# Clock_Generator.net
KiCad netlist of a schematic drawn in Altium Designer
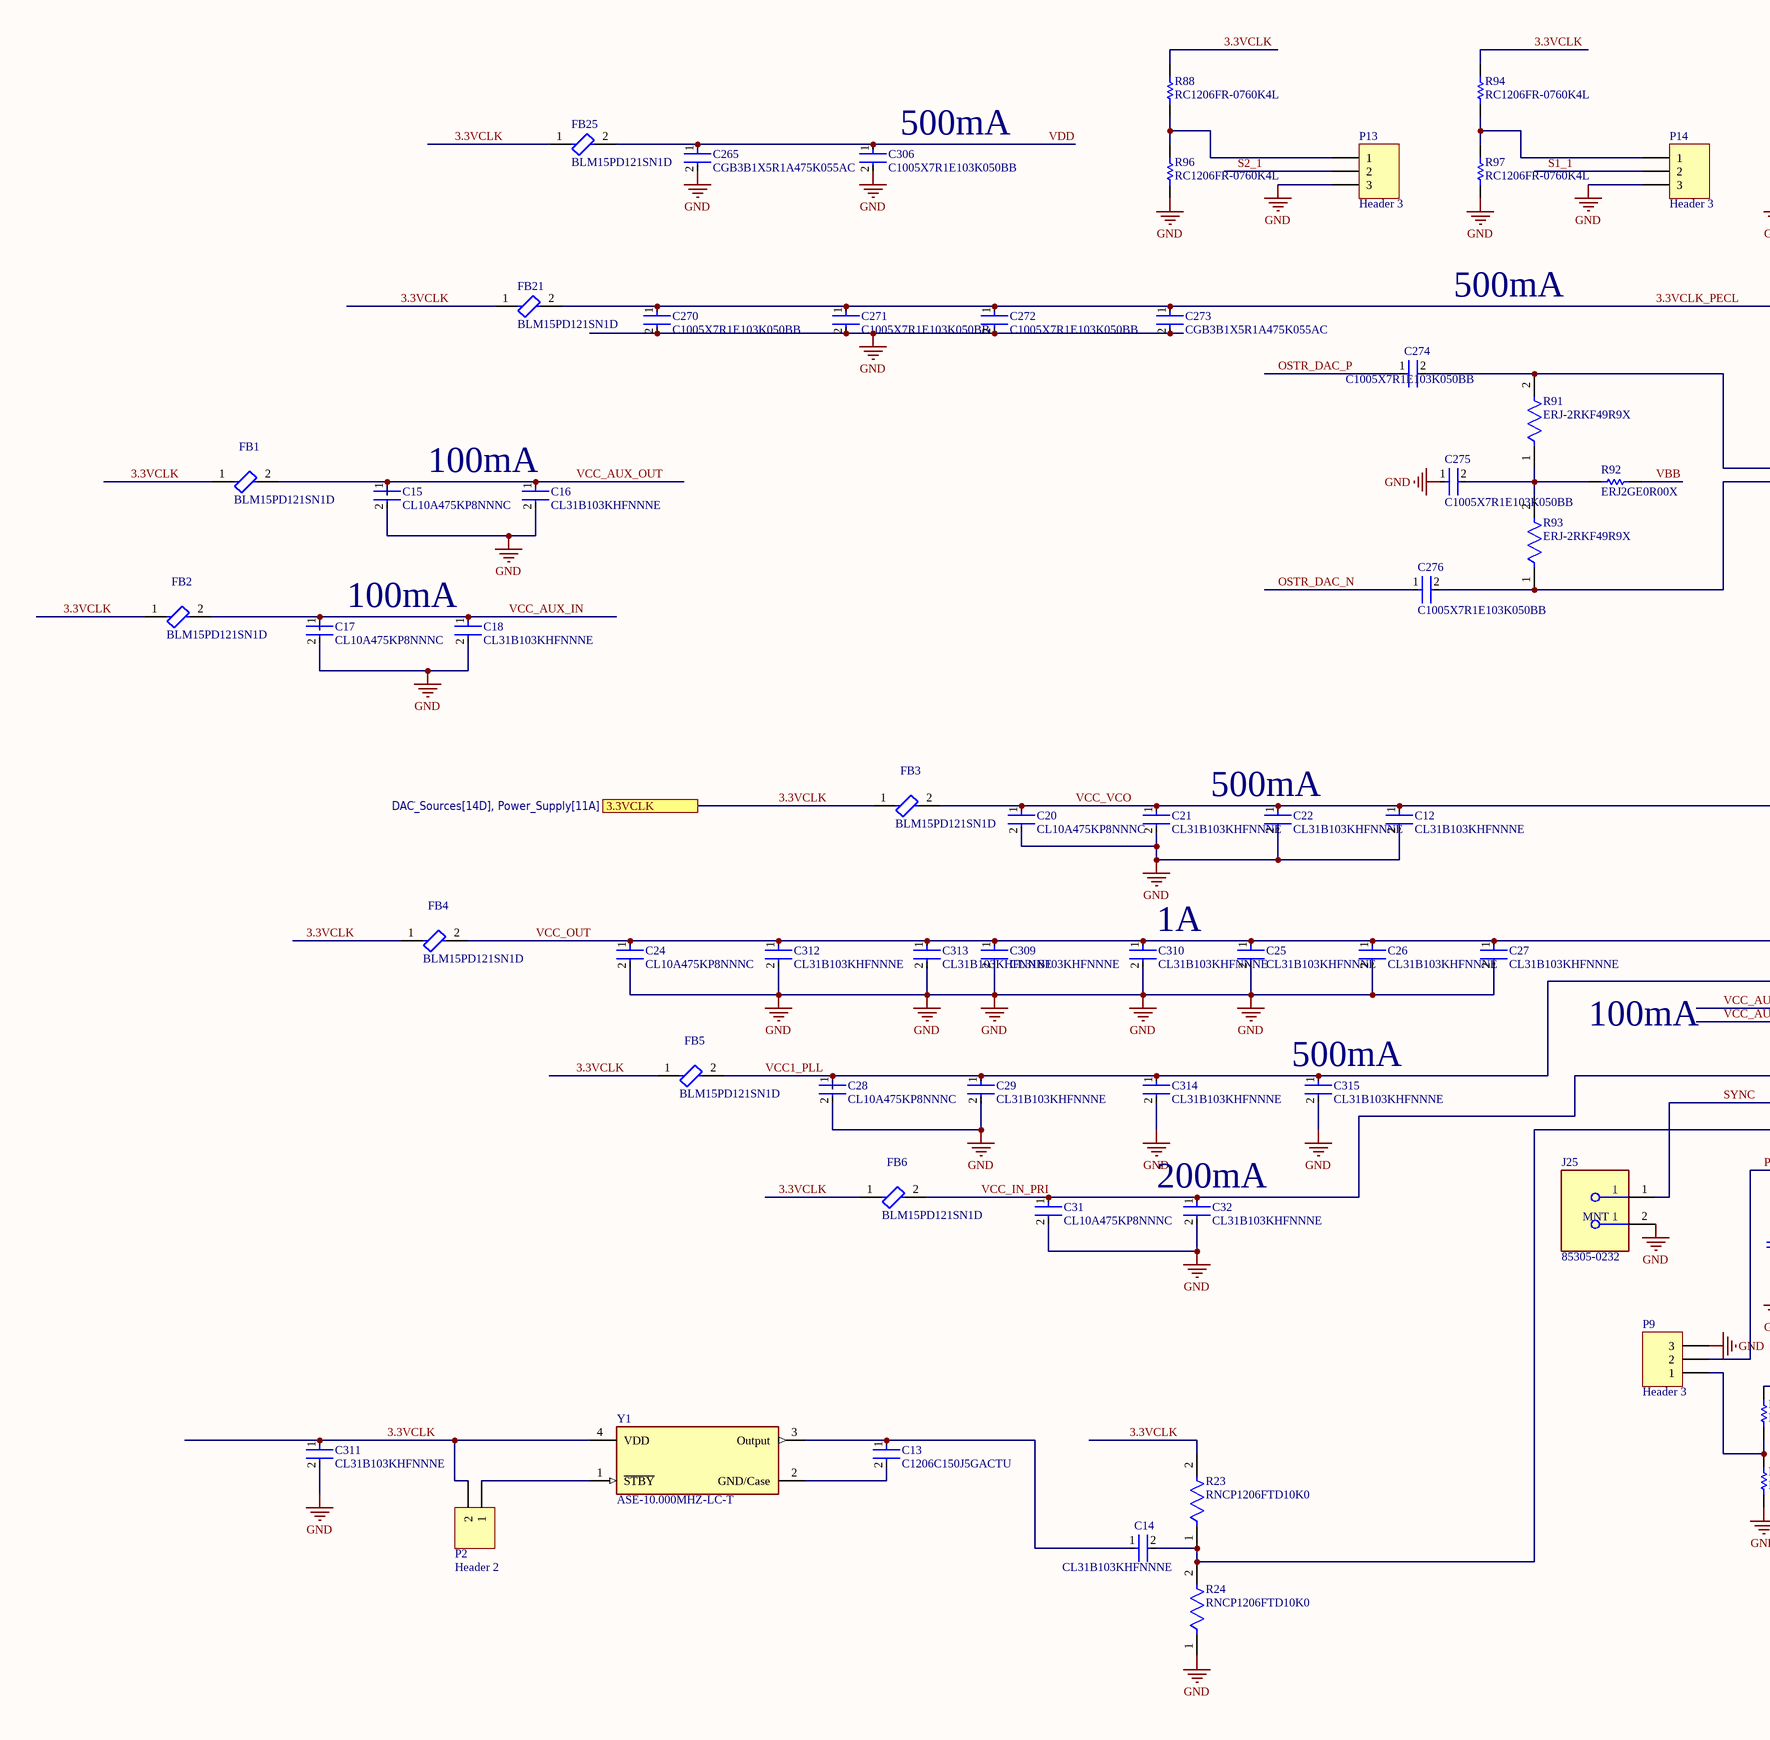
[diagram p0: Clock_Generator.SchDoc, left]
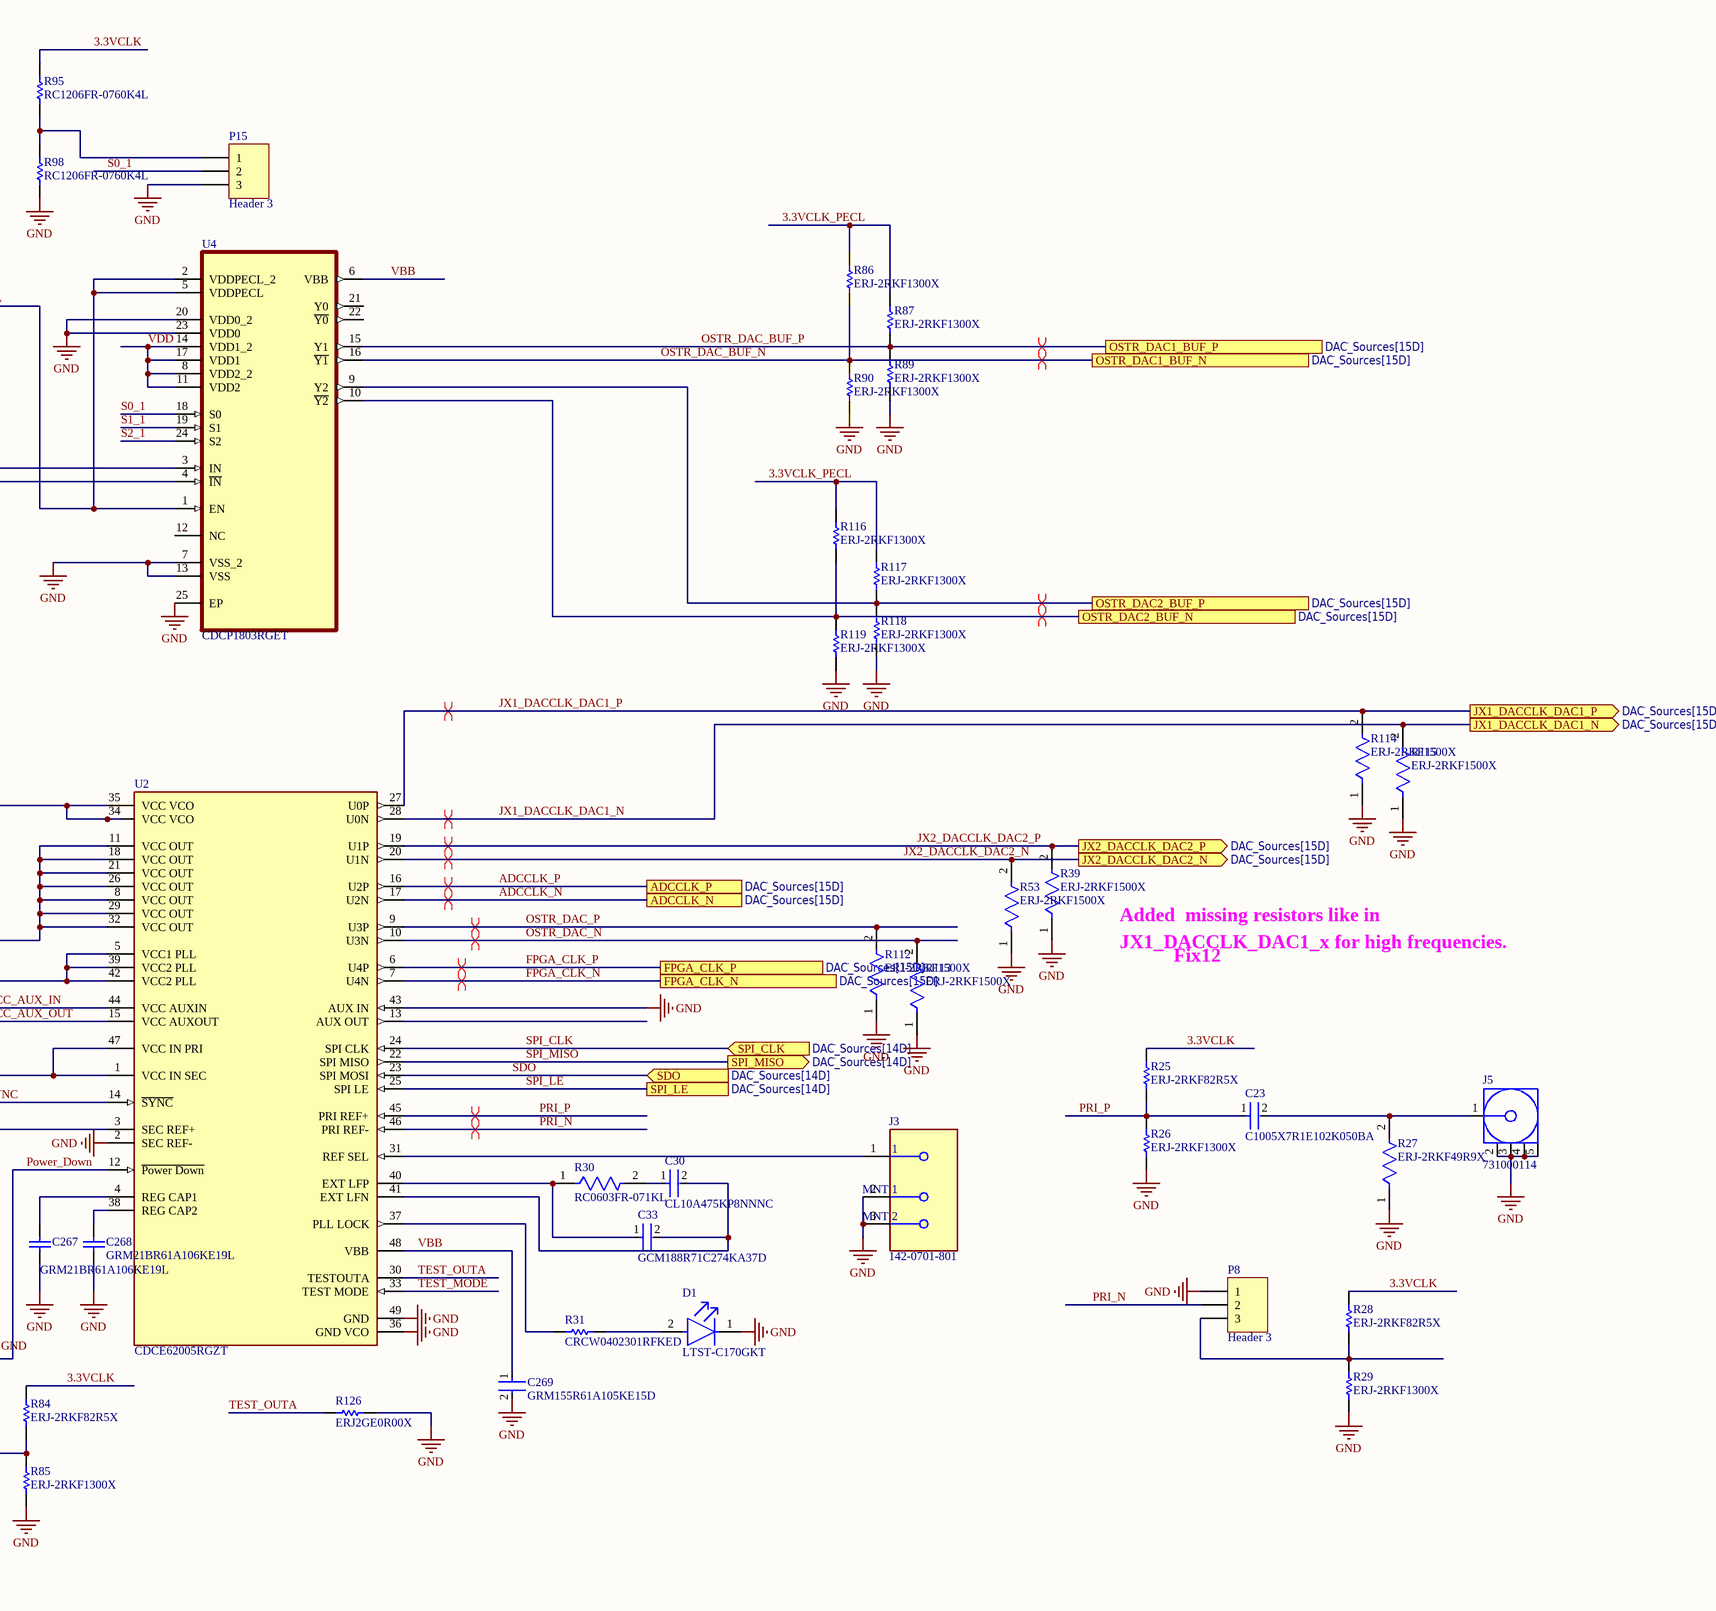
[diagram p1: Clock_Generator.SchDoc, right]

(export (version "E")
  (design (tool "Eeschema 10.0.6"))
  (components
    (comp (ref "C12")
      (value "CL31B103KHFNNNE")
      (footprint "C1206")
      (description "Cap Ceramic 10nF 630V X7R ±10% SMD 1206 +125°C Embossed T/R")
      (fields (field (name "TOLERANCE") "10%") (field (name "VOLTAGE") "630V"))
      (libsource (lib "DACֹֹ_Sources") (part "b4654b650e69147ec39a6b967a45e02"))
    )
    (comp (ref "C13")
      (value "C1206C150J5GACTU")
      (footprint "C1206")
      (description "1206 C 15pF Ceramic Multilayer Capacitor; 50 VDC; +125degC; C0G Dielec; +/-5%")
      (fields (field (name "TOLERANCE") "0.05") (field (name "MANUFACTURER") "KEMET"))
      (libsource (lib "DACֹֹ_Sources") (part "b4654b650e69147ec39a6b967a45e02"))
    )
    (comp (ref "C14")
      (value "CL31B103KHFNNNE")
      (footprint "C1206")
      (description "Cap Ceramic 10nF 630V X7R ±10% SMD 1206 +125°C Embossed T/R")
      (fields (field (name "TOLERANCE") "10%") (field (name "VOLTAGE") "630V"))
      (libsource (lib "DACֹֹ_Sources") (part "b4654b650e69147ec39a6b967a45e02"))
    )
    (comp (ref "C15")
      (value "CL10A475KP8NNNC")
      (footprint "C0603")
      (description "Cap Ceramic 4.7uF 10V X5R ±10% Pad SMD 0603 +85°C T/R")
      (fields (field (name "TOLERANCE") "10%"))
      (libsource (lib "DACֹֹ_Sources") (part "b4654b650e69147ec39a6b967a45e02"))
    )
    (comp (ref "C16")
      (value "CL31B103KHFNNNE")
      (footprint "C1206")
      (description "Cap Ceramic 10nF 630V X7R ±10% SMD 1206 +125°C Embossed T/R")
      (fields (field (name "TOLERANCE") "10%") (field (name "VOLTAGE") "630V"))
      (libsource (lib "DACֹֹ_Sources") (part "b4654b650e69147ec39a6b967a45e02"))
    )
    (comp (ref "C17")
      (value "CL10A475KP8NNNC")
      (footprint "C0603")
      (description "Cap Ceramic 4.7uF 10V X5R ±10% Pad SMD 0603 +85°C T/R")
      (fields (field (name "TOLERANCE") "10%"))
      (libsource (lib "DACֹֹ_Sources") (part "b4654b650e69147ec39a6b967a45e02"))
    )
    (comp (ref "C18")
      (value "CL31B103KHFNNNE")
      (footprint "C1206")
      (description "Cap Ceramic 10nF 630V X7R ±10% SMD 1206 +125°C Embossed T/R")
      (fields (field (name "TOLERANCE") "10%") (field (name "VOLTAGE") "630V"))
      (libsource (lib "DACֹֹ_Sources") (part "b4654b650e69147ec39a6b967a45e02"))
    )
    (comp (ref "C20")
      (value "CL10A475KP8NNNC")
      (footprint "C0603")
      (description "Cap Ceramic 4.7uF 10V X5R ±10% Pad SMD 0603 +85°C T/R")
      (fields (field (name "TOLERANCE") "10%"))
      (libsource (lib "DACֹֹ_Sources") (part "b4654b650e69147ec39a6b967a45e02"))
    )
    (comp (ref "C21")
      (value "CL31B103KHFNNNE")
      (footprint "C1206")
      (description "Cap Ceramic 10nF 630V X7R ±10% SMD 1206 +125°C Embossed T/R")
      (fields (field (name "TOLERANCE") "10%") (field (name "VOLTAGE") "630V"))
      (libsource (lib "DACֹֹ_Sources") (part "b4654b650e69147ec39a6b967a45e02"))
    )
    (comp (ref "C22")
      (value "CL31B103KHFNNNE")
      (footprint "C1206")
      (description "Cap Ceramic 10nF 630V X7R ±10% SMD 1206 +125°C Embossed T/R")
      (fields (field (name "TOLERANCE") "10%") (field (name "VOLTAGE") "630V"))
      (libsource (lib "DACֹֹ_Sources") (part "b4654b650e69147ec39a6b967a45e02"))
    )
    (comp (ref "C23")
      (value "C1005X7R1E102K050BA")
      (footprint "C0402")
      (description "Multilayer Ceramic Capacitors 1nF ±10% 25V X7R SMD 0402")
      (fields (field (name "TOLERANCE") "10%"))
      (libsource (lib "DACֹֹ_Sources") (part "b4654b650e69147ec39a6b967a45e02"))
    )
    (comp (ref "C24")
      (value "CL10A475KP8NNNC")
      (footprint "C0603")
      (description "Cap Ceramic 4.7uF 10V X5R ±10% Pad SMD 0603 +85°C T/R")
      (fields (field (name "TOLERANCE") "10%"))
      (libsource (lib "DACֹֹ_Sources") (part "b4654b650e69147ec39a6b967a45e02"))
    )
    (comp (ref "C25")
      (value "CL31B103KHFNNNE")
      (footprint "C1206")
      (description "Cap Ceramic 10nF 630V X7R ±10% SMD 1206 +125°C Embossed T/R")
      (fields (field (name "TOLERANCE") "10%") (field (name "VOLTAGE") "630V"))
      (libsource (lib "DACֹֹ_Sources") (part "b4654b650e69147ec39a6b967a45e02"))
    )
    (comp (ref "C26")
      (value "CL31B103KHFNNNE")
      (footprint "C1206")
      (description "Cap Ceramic 10nF 630V X7R ±10% SMD 1206 +125°C Embossed T/R")
      (fields (field (name "TOLERANCE") "10%") (field (name "VOLTAGE") "630V"))
      (libsource (lib "DACֹֹ_Sources") (part "b4654b650e69147ec39a6b967a45e02"))
    )
    (comp (ref "C27")
      (value "CL31B103KHFNNNE")
      (footprint "C1206")
      (description "Cap Ceramic 10nF 630V X7R ±10% SMD 1206 +125°C Embossed T/R")
      (fields (field (name "TOLERANCE") "10%") (field (name "VOLTAGE") "630V"))
      (libsource (lib "DACֹֹ_Sources") (part "b4654b650e69147ec39a6b967a45e02"))
    )
    (comp (ref "C28")
      (value "CL10A475KP8NNNC")
      (footprint "C0603")
      (description "Cap Ceramic 4.7uF 10V X5R ±10% Pad SMD 0603 +85°C T/R")
      (fields (field (name "TOLERANCE") "10%"))
      (libsource (lib "DACֹֹ_Sources") (part "b4654b650e69147ec39a6b967a45e02"))
    )
    (comp (ref "C29")
      (value "CL31B103KHFNNNE")
      (footprint "C1206")
      (description "Cap Ceramic 10nF 630V X7R ±10% SMD 1206 +125°C Embossed T/R")
      (fields (field (name "TOLERANCE") "10%") (field (name "VOLTAGE") "630V"))
      (libsource (lib "DACֹֹ_Sources") (part "b4654b650e69147ec39a6b967a45e02"))
    )
    (comp (ref "C30")
      (value "CL10A475KP8NNNC")
      (footprint "C0603")
      (description "Cap Ceramic 4.7uF 10V X5R ±10% Pad SMD 0603 +85°C T/R")
      (fields (field (name "TOLERANCE") "10%"))
      (libsource (lib "DACֹֹ_Sources") (part "b4654b650e69147ec39a6b967a45e02"))
    )
    (comp (ref "C31")
      (value "CL10A475KP8NNNC")
      (footprint "C0603")
      (description "Cap Ceramic 4.7uF 10V X5R ±10% Pad SMD 0603 +85°C T/R")
      (fields (field (name "TOLERANCE") "10%"))
      (libsource (lib "DACֹֹ_Sources") (part "b4654b650e69147ec39a6b967a45e02"))
    )
    (comp (ref "C32")
      (value "CL31B103KHFNNNE")
      (footprint "C1206")
      (description "Cap Ceramic 10nF 630V X7R ±10% SMD 1206 +125°C Embossed T/R")
      (fields (field (name "TOLERANCE") "10%") (field (name "VOLTAGE") "630V"))
      (libsource (lib "DACֹֹ_Sources") (part "b4654b650e69147ec39a6b967a45e02"))
    )
    (comp (ref "C33")
      (value "GCM188R71C274KA37D")
      (footprint "C0603")
      (description "Ceramic Capacitor for Automotive 270nF  ±10% 16VDC X7R 0603 Paper T/R")
      (fields (field (name "TOLERANCE") "10%"))
      (libsource (lib "DACֹֹ_Sources") (part "02cd4be3c70576c341d710602a673aa"))
    )
    (comp (ref "C265")
      (value "CGB3B1X5R1A475K055AC")
      (footprint "C0603")
      (description "CAP CER 4.7UF 10V X5R 0603")
      (fields (field (name "TOLERANCE") "10%"))
      (libsource (lib "DACֹֹ_Sources") (part "b4654b650e69147ec39a6b967a45e02"))
    )
    (comp (ref "C267")
      (value "GRM21BR61A106KE19L")
      (footprint "C0805")
      (description "CAP, Ceramic, 10 uF, 10%, 10 V, 0805, RoHS, Tape and Reel")
      (fields (field (name "MANUFACTURER") "Murata") (field (name "TOLERANCE") "±10%"))
      (libsource (lib "DACֹֹ_Sources") (part "CAP-NP-2"))
    )
    (comp (ref "C268")
      (value "GRM21BR61A106KE19L")
      (footprint "C0805")
      (description "CAP, Ceramic, 10 uF, 10%, 10 V, 0805, RoHS, Tape and Reel")
      (fields (field (name "MANUFACTURER") "Murata") (field (name "TOLERANCE") "±10%"))
      (libsource (lib "DACֹֹ_Sources") (part "CAP-NP-2"))
    )
    (comp (ref "C269")
      (value "GRM155R61A105KE15D")
      (footprint "C0402")
      (description "CAP CER 1UF 10V X5R 0402")
      (fields
        (field (name "OCTOPART") "https://octopart.com/grm155r61a105ke15d-murata-197442")
        (field (name "MANUFACTURER") "Murata")
      )
      (libsource (lib "DACֹֹ_Sources") (part "02cd4be3c70576c341d710602a673aa"))
    )
    (comp (ref "C270")
      (value "C1005X7R1E103K050BB")
      (footprint "C0402")
      (description "Multilayer Ceramic Capacitors 10nF ±10% 25V X7R SMD 0402")
      (fields (field (name "TOLERANCE") "10%") (field (name "VOLTAGE") "25V"))
      (libsource (lib "DACֹֹ_Sources") (part "b4654b650e69147ec39a6b967a45e02"))
    )
    (comp (ref "C271")
      (value "C1005X7R1E103K050BB")
      (footprint "C0402")
      (description "Multilayer Ceramic Capacitors 10nF ±10% 25V X7R SMD 0402")
      (fields (field (name "TOLERANCE") "10%") (field (name "VOLTAGE") "25V"))
      (libsource (lib "DACֹֹ_Sources") (part "b4654b650e69147ec39a6b967a45e02"))
    )
    (comp (ref "C272")
      (value "C1005X7R1E103K050BB")
      (footprint "C0402")
      (description "Multilayer Ceramic Capacitors 10nF ±10% 25V X7R SMD 0402")
      (fields (field (name "TOLERANCE") "10%") (field (name "VOLTAGE") "25V"))
      (libsource (lib "DACֹֹ_Sources") (part "b4654b650e69147ec39a6b967a45e02"))
    )
    (comp (ref "C273")
      (value "CGB3B1X5R1A475K055AC")
      (footprint "C0603")
      (description "CAP CER 4.7UF 10V X5R 0603")
      (fields (field (name "TOLERANCE") "10%"))
      (libsource (lib "DACֹֹ_Sources") (part "b4654b650e69147ec39a6b967a45e02"))
    )
    (comp (ref "C274")
      (value "C1005X7R1E103K050BB")
      (footprint "C0402")
      (description "Multilayer Ceramic Capacitors 10nF ±10% 25V X7R SMD 0402")
      (fields (field (name "TOLERANCE") "10%") (field (name "VOLTAGE") "25V"))
      (libsource (lib "DACֹֹ_Sources") (part "b4654b650e69147ec39a6b967a45e02"))
    )
    (comp (ref "C275")
      (value "C1005X7R1E103K050BB")
      (footprint "C0402")
      (description "Multilayer Ceramic Capacitors 10nF ±10% 25V X7R SMD 0402")
      (fields (field (name "TOLERANCE") "10%") (field (name "VOLTAGE") "25V"))
      (libsource (lib "DACֹֹ_Sources") (part "b4654b650e69147ec39a6b967a45e02"))
    )
    (comp (ref "C276")
      (value "C1005X7R1E103K050BB")
      (footprint "C0402")
      (description "Multilayer Ceramic Capacitors 10nF ±10% 25V X7R SMD 0402")
      (fields (field (name "TOLERANCE") "10%") (field (name "VOLTAGE") "25V"))
      (libsource (lib "DACֹֹ_Sources") (part "b4654b650e69147ec39a6b967a45e02"))
    )
    (comp (ref "C306")
      (value "C1005X7R1E103K050BB")
      (footprint "C0402")
      (description "Multilayer Ceramic Capacitors 10nF ±10% 25V X7R SMD 0402")
      (fields (field (name "TOLERANCE") "10%") (field (name "VOLTAGE") "25V"))
      (libsource (lib "DACֹֹ_Sources") (part "b4654b650e69147ec39a6b967a45e02"))
    )
    (comp (ref "C309")
      (value "CL31B103KHFNNNE")
      (footprint "C1206")
      (description "Cap Ceramic 10nF 630V X7R ±10% SMD 1206 +125°C Embossed T/R")
      (fields (field (name "TOLERANCE") "10%") (field (name "VOLTAGE") "630V"))
      (libsource (lib "DACֹֹ_Sources") (part "b4654b650e69147ec39a6b967a45e02"))
    )
    (comp (ref "C310")
      (value "CL31B103KHFNNNE")
      (footprint "C1206")
      (description "Cap Ceramic 10nF 630V X7R ±10% SMD 1206 +125°C Embossed T/R")
      (fields (field (name "TOLERANCE") "10%") (field (name "VOLTAGE") "630V"))
      (libsource (lib "DACֹֹ_Sources") (part "b4654b650e69147ec39a6b967a45e02"))
    )
    (comp (ref "C311")
      (value "CL31B103KHFNNNE")
      (footprint "C1206")
      (description "Cap Ceramic 10nF 630V X7R ±10% SMD 1206 +125°C Embossed T/R")
      (fields (field (name "TOLERANCE") "10%") (field (name "VOLTAGE") "630V"))
      (libsource (lib "DACֹֹ_Sources") (part "b4654b650e69147ec39a6b967a45e02"))
    )
    (comp (ref "C312")
      (value "CL31B103KHFNNNE")
      (footprint "C1206")
      (description "Cap Ceramic 10nF 630V X7R ±10% SMD 1206 +125°C Embossed T/R")
      (fields (field (name "TOLERANCE") "10%") (field (name "VOLTAGE") "630V"))
      (libsource (lib "DACֹֹ_Sources") (part "b4654b650e69147ec39a6b967a45e02"))
    )
    (comp (ref "C313")
      (value "CL31B103KHFNNNE")
      (footprint "C1206")
      (description "Cap Ceramic 10nF 630V X7R ±10% SMD 1206 +125°C Embossed T/R")
      (fields (field (name "TOLERANCE") "10%") (field (name "VOLTAGE") "630V"))
      (libsource (lib "DACֹֹ_Sources") (part "b4654b650e69147ec39a6b967a45e02"))
    )
    (comp (ref "C314")
      (value "CL31B103KHFNNNE")
      (footprint "C1206")
      (description "Cap Ceramic 10nF 630V X7R ±10% SMD 1206 +125°C Embossed T/R")
      (fields (field (name "TOLERANCE") "10%") (field (name "VOLTAGE") "630V"))
      (libsource (lib "DACֹֹ_Sources") (part "b4654b650e69147ec39a6b967a45e02"))
    )
    (comp (ref "C315")
      (value "CL31B103KHFNNNE")
      (footprint "C1206")
      (description "Cap Ceramic 10nF 630V X7R ±10% SMD 1206 +125°C Embossed T/R")
      (fields (field (name "TOLERANCE") "10%") (field (name "VOLTAGE") "630V"))
      (libsource (lib "DACֹֹ_Sources") (part "b4654b650e69147ec39a6b967a45e02"))
    )
    (comp (ref "D1")
      (value "LTST-C170GKT")
      (footprint "FP-LTST-C170GKT-MFG")
      (description "LED GREEN CLEAR SMD")
      (fields (field (name "VOLTAGE") "5V"))
      (libsource (lib "DACֹֹ_Sources") (part "8706943c75ba83719d021d2fdc84c58"))
    )
    (comp (ref "FB1")
      (value "BLM15PD121SN1D")
      (footprint "BLM15")
      (description "Chip Ferrite Bead, 0402, 120Ω @ 100MHz, 0.09Ω, 25%, 1.3A")
      (fields (field (name "TOLERANCE") "25%"))
      (libsource (lib "DACֹֹ_Sources") (part "5f30dd21d616792df468990f7003faa"))
    )
    (comp (ref "FB2")
      (value "BLM15PD121SN1D")
      (footprint "BLM15")
      (description "Chip Ferrite Bead, 0402, 120Ω @ 100MHz, 0.09Ω, 25%, 1.3A")
      (fields (field (name "TOLERANCE") "25%"))
      (libsource (lib "DACֹֹ_Sources") (part "5f30dd21d616792df468990f7003faa"))
    )
    (comp (ref "FB3")
      (value "BLM15PD121SN1D")
      (footprint "BLM15")
      (description "Chip Ferrite Bead, 0402, 120Ω @ 100MHz, 0.09Ω, 25%, 1.3A")
      (fields (field (name "TOLERANCE") "25%"))
      (libsource (lib "DACֹֹ_Sources") (part "5f30dd21d616792df468990f7003faa"))
    )
    (comp (ref "FB4")
      (value "BLM15PD121SN1D")
      (footprint "BLM15")
      (description "Chip Ferrite Bead, 0402, 120Ω @ 100MHz, 0.09Ω, 25%, 1.3A")
      (fields (field (name "TOLERANCE") "25%"))
      (libsource (lib "DACֹֹ_Sources") (part "5f30dd21d616792df468990f7003faa"))
    )
    (comp (ref "FB5")
      (value "BLM15PD121SN1D")
      (footprint "BLM15")
      (description "Chip Ferrite Bead, 0402, 120Ω @ 100MHz, 0.09Ω, 25%, 1.3A")
      (fields (field (name "TOLERANCE") "25%"))
      (libsource (lib "DACֹֹ_Sources") (part "5f30dd21d616792df468990f7003faa"))
    )
    (comp (ref "FB6")
      (value "BLM15PD121SN1D")
      (footprint "BLM15")
      (description "Chip Ferrite Bead, 0402, 120Ω @ 100MHz, 0.09Ω, 25%, 1.3A")
      (fields (field (name "TOLERANCE") "25%"))
      (libsource (lib "DACֹֹ_Sources") (part "5f30dd21d616792df468990f7003faa"))
    )
    (comp (ref "FB21")
      (value "BLM15PD121SN1D")
      (footprint "BLM15")
      (description "Chip Ferrite Bead, 0402, 120Ω @ 100MHz, 0.09Ω, 25%, 1.3A")
      (fields (field (name "TOLERANCE") "25%"))
      (libsource (lib "DACֹֹ_Sources") (part "5f30dd21d616792df468990f7003faa"))
    )
    (comp (ref "FB25")
      (value "BLM15PD121SN1D")
      (footprint "BLM15")
      (description "Chip Ferrite Bead, 0402, 120Ω @ 100MHz, 0.09Ω, 25%, 1.3A")
      (fields (field (name "TOLERANCE") "25%"))
      (libsource (lib "DACֹֹ_Sources") (part "5f30dd21d616792df468990f7003faa"))
    )
    (comp (ref "J3")
      (value "142-0701-801")
      (footprint "FP-142-0701-801-MFG")
      (description "CONN SMA JACK STR 50OHM EDGE MNT")
      (libsource (lib "DACֹֹ_Sources") (part "89929399afe843c8b6880c6cbd0f99a"))
    )
    (comp (ref "J5")
      (value "731000114")
      (footprint "MOLX-731000114_V")
      (description "SMA Right-Angle PCB Jack Receptacle, Brass Body, Gold Plated, 50 Ohm, 5-Pin THD, RoHS, Tray")
      (fields (field (name "MANUFACTURER") "Molex"))
      (libsource (lib "DACֹֹ_Sources") (part "CN-S-4F-RF5"))
    )
    (comp (ref "J25")
      (value "85305-0232")
      (footprint "FP-85305-0232-MFG")
      (description "CONN SMP PLUG STR 50 OHM SMD")
      (libsource (lib "DACֹֹ_Sources") (part "d2a53f3a980517e545f22a6fb6569cc"))
    )
    (comp (ref "P2")
      (value "Header 2")
      (footprint "HEADER_2X1")
      (description "Header, 2-Pin")
      (fields (field (name "PUBLISHER") "Altium Limited"))
      (libsource (lib "DACֹֹ_Sources") (part "Header 2"))
    )
    (comp (ref "P8")
      (value "Header 3")
      (footprint "HEADER_3X1")
      (description "Header, 3-Pin")
      (fields (field (name "PUBLISHER") "Altium Limited"))
      (libsource (lib "DACֹֹ_Sources") (part "Header 3"))
    )
    (comp (ref "P9")
      (value "Header 3")
      (footprint "HEADER_3X1")
      (description "Header, 3-Pin")
      (fields (field (name "PUBLISHER") "Altium Limited"))
      (libsource (lib "") (part "Header 3_1"))
    )
    (comp (ref "P13")
      (value "Header 3")
      (footprint "HEADER_3X1")
      (description "Header, 3-Pin")
      (fields (field (name "PUBLISHER") "Altium Limited"))
      (libsource (lib "DACֹֹ_Sources") (part "Header 3"))
    )
    (comp (ref "P14")
      (value "Header 3")
      (footprint "HEADER_3X1")
      (description "Header, 3-Pin")
      (fields (field (name "PUBLISHER") "Altium Limited"))
      (libsource (lib "DACֹֹ_Sources") (part "Header 3"))
    )
    (comp (ref "P15")
      (value "Header 3")
      (footprint "HEADER_3X1")
      (description "Header, 3-Pin")
      (fields (field (name "PUBLISHER") "Altium Limited"))
      (libsource (lib "DACֹֹ_Sources") (part "Header 3"))
    )
    (comp (ref "R23")
      (value "RNCP1206FTD10K0")
      (footprint "R1206")
      (description "10kΩ ±1% 0.5W 1206 High Power Anti-Sulfur Thin Film Chip Resistor")
      (fields (field (name "TOLERANCE") "1%"))
      (libsource (lib "DACֹֹ_Sources") (part "1029c3af85768c4190bb7ad29bc67b5"))
    )
    (comp (ref "R24")
      (value "RNCP1206FTD10K0")
      (footprint "R1206")
      (description "10kΩ ±1% 0.5W 1206 High Power Anti-Sulfur Thin Film Chip Resistor")
      (fields (field (name "TOLERANCE") "1%"))
      (libsource (lib "DACֹֹ_Sources") (part "1029c3af85768c4190bb7ad29bc67b5"))
    )
    (comp (ref "R25")
      (value "ERJ-2RKF82R5X")
      (footprint "R0402")
      (fields (field (name "MANUFACTURER") "Panasonic"))
      (libsource (lib "DACֹֹ_Sources") (part "RES"))
    )
    (comp (ref "R26")
      (value "ERJ-2RKF1300X")
      (footprint "R0402")
      (fields (field (name "MANUFACTURER") "Panasonic"))
      (libsource (lib "DACֹֹ_Sources") (part "RES"))
    )
    (comp (ref "R27")
      (value "ERJ-2RKF49R9X")
      (footprint "R0402")
      (description "RES SMD 49.9 OHM 1% 1/10W 0402")
      (fields (field (name "TOLERANCE") "1%"))
      (libsource (lib "DACֹֹ_Sources") (part "8db39607336c341a927600551d01821"))
    )
    (comp (ref "R28")
      (value "ERJ-2RKF82R5X")
      (footprint "R0402")
      (fields (field (name "MANUFACTURER") "Panasonic"))
      (libsource (lib "DACֹֹ_Sources") (part "RES"))
    )
    (comp (ref "R29")
      (value "ERJ-2RKF1300X")
      (footprint "R0402")
      (fields (field (name "MANUFACTURER") "Panasonic"))
      (libsource (lib "DACֹֹ_Sources") (part "RES"))
    )
    (comp (ref "R30")
      (value "RC0603FR-071KL")
      (footprint "R0603")
      (description "RES 1K OHM 1% 1/10W 0603")
      (fields (field (name "TOLERANCE") "1%"))
      (libsource (lib "DACֹֹ_Sources") (part "1029c3af85768c4190bb7ad29bc67b5"))
    )
    (comp (ref "R31")
      (value "CRCW0402301RFKED")
      (footprint "R0402")
      (fields (field (name "MANUFACTURER") "Vishay Dale"))
      (libsource (lib "DACֹֹ_Sources") (part "RES"))
    )
    (comp (ref "R39")
      (value "ERJ-2RKF1500X")
      (footprint "R0402")
      (description "RES SMD 150 OHM 1% 1/10W 0402")
      (fields (field (name "TOLERANCE") "1%"))
      (libsource (lib "DACֹֹ_Sources") (part "1029c3af85768c4190bb7ad29bc67b5"))
    )
    (comp (ref "R53")
      (value "ERJ-2RKF1500X")
      (footprint "R0402")
      (description "RES SMD 150 OHM 1% 1/10W 0402")
      (fields (field (name "TOLERANCE") "1%"))
      (libsource (lib "DACֹֹ_Sources") (part "1029c3af85768c4190bb7ad29bc67b5"))
    )
    (comp (ref "R84")
      (value "ERJ-2RKF82R5X")
      (footprint "R0402")
      (fields (field (name "MANUFACTURER") "Panasonic"))
      (libsource (lib "DACֹֹ_Sources") (part "RES"))
    )
    (comp (ref "R85")
      (value "ERJ-2RKF1300X")
      (footprint "R0402")
      (fields (field (name "MANUFACTURER") "Panasonic"))
      (libsource (lib "DACֹֹ_Sources") (part "RES"))
    )
    (comp (ref "R86")
      (value "ERJ-2RKF1300X")
      (footprint "R0402")
      (fields (field (name "MANUFACTURER") "Panasonic"))
      (libsource (lib "DACֹֹ_Sources") (part "RES"))
    )
    (comp (ref "R87")
      (value "ERJ-2RKF1300X")
      (footprint "R0402")
      (fields (field (name "MANUFACTURER") "Panasonic"))
      (libsource (lib "DACֹֹ_Sources") (part "RES"))
    )
    (comp (ref "R88")
      (value "RC1206FR-0760K4L")
      (footprint "R1206")
      (fields (field (name "MANUFACTURER") "Yageo"))
      (libsource (lib "DACֹֹ_Sources") (part "RES"))
    )
    (comp (ref "R89")
      (value "ERJ-2RKF1300X")
      (footprint "R0402")
      (fields (field (name "MANUFACTURER") "Panasonic"))
      (libsource (lib "DACֹֹ_Sources") (part "RES"))
    )
    (comp (ref "R90")
      (value "ERJ-2RKF1300X")
      (footprint "R0402")
      (fields (field (name "MANUFACTURER") "Panasonic"))
      (libsource (lib "DACֹֹ_Sources") (part "RES"))
    )
    (comp (ref "R91")
      (value "ERJ-2RKF49R9X")
      (footprint "R0402")
      (description "RES SMD 49.9 OHM 1% 1/10W 0402")
      (fields (field (name "TOLERANCE") "1%"))
      (libsource (lib "DACֹֹ_Sources") (part "8db39607336c341a927600551d01821"))
    )
    (comp (ref "R92")
      (value "ERJ2GE0R00X")
      (footprint "R0402")
      (description "Chip Resistor, 0 Ohm, 0.1 W, -55 to 155 degC, 0402 (1005 Metric), RoHS, Tape and Reel")
      (fields (field (name "MANUFACTURER") "Panasonic") (field (name "TOLERANCE") "5%"))
      (libsource (lib "DACֹֹ_Sources") (part "RES-2"))
    )
    (comp (ref "R93")
      (value "ERJ-2RKF49R9X")
      (footprint "R0402")
      (description "RES SMD 49.9 OHM 1% 1/10W 0402")
      (fields (field (name "TOLERANCE") "1%"))
      (libsource (lib "DACֹֹ_Sources") (part "8db39607336c341a927600551d01821"))
    )
    (comp (ref "R94")
      (value "RC1206FR-0760K4L")
      (footprint "R1206")
      (fields (field (name "MANUFACTURER") "Yageo"))
      (libsource (lib "DACֹֹ_Sources") (part "RES"))
    )
    (comp (ref "R95")
      (value "RC1206FR-0760K4L")
      (footprint "R1206")
      (fields (field (name "MANUFACTURER") "Yageo"))
      (libsource (lib "DACֹֹ_Sources") (part "RES"))
    )
    (comp (ref "R96")
      (value "RC1206FR-0760K4L")
      (footprint "R1206")
      (fields (field (name "MANUFACTURER") "Yageo"))
      (libsource (lib "DACֹֹ_Sources") (part "RES"))
    )
    (comp (ref "R97")
      (value "RC1206FR-0760K4L")
      (footprint "R1206")
      (fields (field (name "MANUFACTURER") "Yageo"))
      (libsource (lib "DACֹֹ_Sources") (part "RES"))
    )
    (comp (ref "R98")
      (value "RC1206FR-0760K4L")
      (footprint "R1206")
      (fields (field (name "MANUFACTURER") "Yageo"))
      (libsource (lib "DACֹֹ_Sources") (part "RES"))
    )
    (comp (ref "R112")
      (value "ERJ-2RKF1500X")
      (footprint "R0402")
      (description "RES SMD 150 OHM 1% 1/10W 0402")
      (fields (field (name "TOLERANCE") "1%"))
      (libsource (lib "DACֹֹ_Sources") (part "1029c3af85768c4190bb7ad29bc67b5"))
    )
    (comp (ref "R113")
      (value "ERJ-2RKF1500X")
      (footprint "R0402")
      (description "RES SMD 150 OHM 1% 1/10W 0402")
      (fields (field (name "TOLERANCE") "1%"))
      (libsource (lib "DACֹֹ_Sources") (part "1029c3af85768c4190bb7ad29bc67b5"))
    )
    (comp (ref "R114")
      (value "ERJ-2RKF1500X")
      (footprint "R0402")
      (description "RES SMD 150 OHM 1% 1/10W 0402")
      (fields (field (name "TOLERANCE") "1%"))
      (libsource (lib "DACֹֹ_Sources") (part "1029c3af85768c4190bb7ad29bc67b5"))
    )
    (comp (ref "R115")
      (value "ERJ-2RKF1500X")
      (footprint "R0402")
      (description "RES SMD 150 OHM 1% 1/10W 0402")
      (fields (field (name "TOLERANCE") "1%"))
      (libsource (lib "DACֹֹ_Sources") (part "1029c3af85768c4190bb7ad29bc67b5"))
    )
    (comp (ref "R116")
      (value "ERJ-2RKF1300X")
      (footprint "R0402")
      (fields (field (name "MANUFACTURER") "Panasonic"))
      (libsource (lib "DACֹֹ_Sources") (part "RES"))
    )
    (comp (ref "R117")
      (value "ERJ-2RKF1300X")
      (footprint "R0402")
      (fields (field (name "MANUFACTURER") "Panasonic"))
      (libsource (lib "DACֹֹ_Sources") (part "RES"))
    )
    (comp (ref "R118")
      (value "ERJ-2RKF1300X")
      (footprint "R0402")
      (fields (field (name "MANUFACTURER") "Panasonic"))
      (libsource (lib "DACֹֹ_Sources") (part "RES"))
    )
    (comp (ref "R119")
      (value "ERJ-2RKF1300X")
      (footprint "R0402")
      (fields (field (name "MANUFACTURER") "Panasonic"))
      (libsource (lib "DACֹֹ_Sources") (part "RES"))
    )
    (comp (ref "R126")
      (value "ERJ2GE0R00X")
      (footprint "R0402")
      (description "Chip Resistor, 0 Ohm, 0.1 W, -55 to 155 degC, 0402 (1005 Metric), RoHS, Tape and Reel")
      (fields (field (name "MANUFACTURER") "Panasonic") (field (name "TOLERANCE") "5%"))
      (libsource (lib "DACֹֹ_Sources") (part "RES-2"))
    )
    (comp (ref "U2")
      (value "CDCE62005RGZT")
      (footprint "FP-RGZ0048D-IPC_A")
      (description "IC CLK SYNTH/JITTER CLEANR 48QFN")
      (libsource (lib "DACֹֹ_Sources") (part "79e6de338fe35b6fdc3d186d6aa1691"))
    )
    (comp (ref "U4")
      (value "CDCP1803RGET")
      (footprint "QFN25")
      (description "1:3 LVPECL clock buffer with programable divider")
      (fields (field (name "MF") "Texas Instruments"))
      (libsource (lib "DACֹֹ_Sources") (part "CDCP1803RGET"))
    )
    (comp (ref "Y1")
      (value "ASE-10.000MHZ-LC-T")
      (footprint "ASE")
      (description "XTAL Oscillator 10MHz ±50ppm CMOS 3.3V 4-SMD 3.2mm x 2.5mm")
      (libsource (lib "DACֹֹ_Sources") (part "61a724e6190563596ac712fef61ad37"))
    )
  )
  (nets
    (net (code "1") (name "/3.3VCLK") (class "Default")
      (node (ref "C311") (pin "1") (pinfunction "1_1") (pintype "passive"))
      (node (ref "FB1") (pin "1") (pinfunction "1_1") (pintype "passive"))
      (node (ref "FB2") (pin "1") (pinfunction "1_1") (pintype "passive"))
      (node (ref "FB21") (pin "1") (pinfunction "1_1") (pintype "passive"))
      (node (ref "FB25") (pin "1") (pinfunction "1_1") (pintype "passive"))
      (node (ref "FB3") (pin "1") (pinfunction "1_1") (pintype "passive"))
      (node (ref "FB4") (pin "1") (pinfunction "1_1") (pintype "passive"))
      (node (ref "FB5") (pin "1") (pinfunction "1_1") (pintype "passive"))
      (node (ref "FB6") (pin "1") (pinfunction "1_1") (pintype "passive"))
      (node (ref "P2") (pin "2") (pinfunction "2_2") (pintype "passive"))
      (node (ref "R23") (pin "2") (pinfunction "2_2") (pintype "passive"))
      (node (ref "R25") (pin "2") (pinfunction "2_2") (pintype "passive"))
      (node (ref "R28") (pin "2") (pinfunction "2_2") (pintype "passive"))
      (node (ref "R84") (pin "2") (pinfunction "2_2") (pintype "passive"))
      (node (ref "R88") (pin "2") (pinfunction "2_2") (pintype "passive"))
      (node (ref "R94") (pin "2") (pinfunction "2_2") (pintype "passive"))
      (node (ref "R95") (pin "2") (pinfunction "2_2") (pintype "passive"))
      (node (ref "Y1") (pin "4") (pinfunction "VDD_4") (pintype "power_in"))
    )
    (net (code "2") (name "/3.3VCLK_PECL") (class "Default")
      (node (ref "C270") (pin "1") (pinfunction "1_1") (pintype "passive"))
      (node (ref "C271") (pin "1") (pinfunction "1_1") (pintype "passive"))
      (node (ref "C272") (pin "1") (pinfunction "1_1") (pintype "passive"))
      (node (ref "C273") (pin "1") (pinfunction "1_1") (pintype "passive"))
      (node (ref "FB21") (pin "2") (pinfunction "2_2") (pintype "passive"))
      (node (ref "R116") (pin "2") (pinfunction "2_2") (pintype "passive"))
      (node (ref "R117") (pin "2") (pinfunction "2_2") (pintype "passive"))
      (node (ref "R86") (pin "2") (pinfunction "2_2") (pintype "passive"))
      (node (ref "R87") (pin "2") (pinfunction "2_2") (pintype "passive"))
      (node (ref "U4") (pin "1") (pinfunction "EN_1") (pintype "input"))
      (node (ref "U4") (pin "2") (pinfunction "VDDPECL_2_2") (pintype "power_in"))
      (node (ref "U4") (pin "5") (pinfunction "VDDPECL_5") (pintype "power_in"))
    )
    (net (code "3") (name "/ADCCLK_N") (class "Default")
      (node (ref "U2") (pin "17") (pinfunction "U2N_17") (pintype "output"))
    )
    (net (code "4") (name "/ADCCLK_P") (class "Default")
      (node (ref "U2") (pin "16") (pinfunction "U2P_16") (pintype "output"))
    )
    (net (code "5") (name "/FPGA_CLK_N") (class "Default")
      (node (ref "U2") (pin "7") (pinfunction "U4N_7") (pintype "output"))
    )
    (net (code "6") (name "/FPGA_CLK_P") (class "Default")
      (node (ref "U2") (pin "6") (pinfunction "U4P_6") (pintype "output"))
    )
    (net (code "7") (name "/JX1_DACCLK_DAC1_N") (class "Default")
      (node (ref "R115") (pin "2") (pinfunction "2_2") (pintype "passive"))
      (node (ref "U2") (pin "28") (pinfunction "U0N_28") (pintype "output"))
    )
    (net (code "8") (name "/JX1_DACCLK_DAC1_P") (class "Default")
      (node (ref "R114") (pin "2") (pinfunction "2_2") (pintype "passive"))
      (node (ref "U2") (pin "27") (pinfunction "U0P_27") (pintype "output"))
    )
    (net (code "9") (name "/JX2_DACCLK_DAC2_N") (class "Default")
      (node (ref "R53") (pin "2") (pinfunction "2_2") (pintype "passive"))
      (node (ref "U2") (pin "20") (pinfunction "U1N_20") (pintype "output"))
    )
    (net (code "10") (name "/JX2_DACCLK_DAC2_P") (class "Default")
      (node (ref "R39") (pin "2") (pinfunction "2_2") (pintype "passive"))
      (node (ref "U2") (pin "19") (pinfunction "U1P_19") (pintype "output"))
    )
    (net (code "11") (name "/OSTR_DAC2_BUF_N") (class "Default")
      (node (ref "R116") (pin "1") (pinfunction "1_1") (pintype "passive"))
      (node (ref "R119") (pin "2") (pinfunction "2_2") (pintype "passive"))
      (node (ref "U4") (pin "10") (pinfunction "~{Y2}_10") (pintype "output"))
    )
    (net (code "12") (name "/OSTR_DAC2_BUF_P") (class "Default")
      (node (ref "R117") (pin "1") (pinfunction "1_1") (pintype "passive"))
      (node (ref "R118") (pin "2") (pinfunction "2_2") (pintype "passive"))
      (node (ref "U4") (pin "9") (pinfunction "Y2_9") (pintype "output"))
    )
    (net (code "13") (name "/OSTR_DAC_BUF_N") (class "Default")
      (node (ref "R86") (pin "1") (pinfunction "1_1") (pintype "passive"))
      (node (ref "R90") (pin "2") (pinfunction "2_2") (pintype "passive"))
      (node (ref "U4") (pin "16") (pinfunction "~{Y1}_16") (pintype "output"))
    )
    (net (code "14") (name "/OSTR_DAC_BUF_P") (class "Default")
      (node (ref "R87") (pin "1") (pinfunction "1_1") (pintype "passive"))
      (node (ref "R89") (pin "2") (pinfunction "2_2") (pintype "passive"))
      (node (ref "U4") (pin "15") (pinfunction "Y1_15") (pintype "output"))
    )
    (net (code "15") (name "/OSTR_DAC_N") (class "Default")
      (node (ref "C276") (pin "1") (pinfunction "1_1") (pintype "passive"))
      (node (ref "R113") (pin "2") (pinfunction "2_2") (pintype "passive"))
      (node (ref "U2") (pin "10") (pinfunction "U3N_10") (pintype "output"))
    )
    (net (code "16") (name "/OSTR_DAC_P") (class "Default")
      (node (ref "C274") (pin "1") (pinfunction "1_1") (pintype "passive"))
      (node (ref "R112") (pin "2") (pinfunction "2_2") (pintype "passive"))
      (node (ref "U2") (pin "9") (pinfunction "U3P_9") (pintype "output"))
    )
    (net (code "17") (name "/PRI_N") (class "Default")
      (node (ref "P8") (pin "2") (pinfunction "2_2") (pintype "passive"))
      (node (ref "U2") (pin "46") (pinfunction "PRI_REF-_46") (pintype "input"))
    )
    (net (code "18") (name "/PRI_P") (class "Default")
      (node (ref "C23") (pin "1") (pinfunction "1_1") (pintype "passive"))
      (node (ref "R25") (pin "1") (pinfunction "1_1") (pintype "passive"))
      (node (ref "R26") (pin "2") (pinfunction "2_2") (pintype "passive"))
      (node (ref "U2") (pin "45") (pinfunction "PRI_REF+_45") (pintype "input"))
    )
    (net (code "19") (name "/Power_Down") (class "Default")
      (node (ref "P9") (pin "2") (pinfunction "2_2") (pintype "passive"))
      (node (ref "U2") (pin "12") (pinfunction "~{Power_Down}_12") (pintype "input"))
    )
    (net (code "20") (name "/S0_1") (class "Default")
      (node (ref "P15") (pin "2") (pinfunction "2_2") (pintype "passive"))
      (node (ref "U4") (pin "18") (pinfunction "S0_18") (pintype "input"))
    )
    (net (code "21") (name "/S1_1") (class "Default")
      (node (ref "P14") (pin "2") (pinfunction "2_2") (pintype "passive"))
      (node (ref "U4") (pin "19") (pinfunction "S1_19") (pintype "input"))
    )
    (net (code "22") (name "/S2_1") (class "Default")
      (node (ref "P13") (pin "2") (pinfunction "2_2") (pintype "passive"))
      (node (ref "U4") (pin "24") (pinfunction "S2_24") (pintype "input"))
    )
    (net (code "23") (name "/SDO") (class "Default")
      (node (ref "U2") (pin "23") (pinfunction "SPI_MOSI_23") (pintype "input"))
    )
    (net (code "24") (name "/SPI_CLK") (class "Default")
      (node (ref "U2") (pin "24") (pinfunction "SPI_CLK_24") (pintype "input"))
    )
    (net (code "25") (name "/SPI_LE") (class "Default")
      (node (ref "U2") (pin "25") (pinfunction "SPI_LE_25") (pintype "input"))
    )
    (net (code "26") (name "/SPI_MISO") (class "Default")
      (node (ref "U2") (pin "22") (pinfunction "SPI_MISO_22") (pintype "output"))
    )
    (net (code "27") (name "/SYNC") (class "Default")
      (node (ref "J25") (pin "1") (pinfunction "1_1") (pintype "passive"))
      (node (ref "U2") (pin "14") (pinfunction "~{SYNC}_14") (pintype "input"))
    )
    (net (code "28") (name "/TEST_MODE") (class "Default")
      (node (ref "U2") (pin "33") (pinfunction "TEST_MODE_33") (pintype "input"))
    )
    (net (code "29") (name "/TEST_OUTA") (class "Default")
      (node (ref "R126") (pin "1") (pinfunction "1_1") (pintype "passive"))
      (node (ref "U2") (pin "30") (pinfunction "TESTOUTA_30") (pintype "passive"))
    )
    (net (code "30") (name "/VBB") (class "Default")
      (node (ref "C269") (pin "1") (pinfunction "1_1") (pintype "passive"))
      (node (ref "R92") (pin "2") (pinfunction "2_2") (pintype "passive"))
      (node (ref "U2") (pin "48") (pinfunction "VBB_48") (pintype "passive"))
      (node (ref "U4") (pin "6") (pinfunction "VBB_6") (pintype "output"))
    )
    (net (code "31") (name "/VCC1_PLL") (class "Default")
      (node (ref "C28") (pin "1") (pinfunction "1_1") (pintype "passive"))
      (node (ref "C29") (pin "1") (pinfunction "1_1") (pintype "passive"))
      (node (ref "C314") (pin "1") (pinfunction "1_1") (pintype "passive"))
      (node (ref "C315") (pin "1") (pinfunction "1_1") (pintype "passive"))
      (node (ref "FB5") (pin "2") (pinfunction "2_2") (pintype "passive"))
      (node (ref "U2") (pin "39") (pinfunction "VCC2_PLL_39") (pintype "power_in"))
      (node (ref "U2") (pin "42") (pinfunction "VCC2_PLL_42") (pintype "power_in"))
      (node (ref "U2") (pin "5") (pinfunction "VCC1_PLL_5") (pintype "power_in"))
    )
    (net (code "32") (name "/VCC_AUX_IN") (class "Default")
      (node (ref "C17") (pin "1") (pinfunction "1_1") (pintype "passive"))
      (node (ref "C18") (pin "1") (pinfunction "1_1") (pintype "passive"))
      (node (ref "FB2") (pin "2") (pinfunction "2_2") (pintype "passive"))
      (node (ref "U2") (pin "44") (pinfunction "VCC_AUXIN_44") (pintype "power_in"))
    )
    (net (code "33") (name "/VCC_AUX_OUT") (class "Default")
      (node (ref "C15") (pin "1") (pinfunction "1_1") (pintype "passive"))
      (node (ref "C16") (pin "1") (pinfunction "1_1") (pintype "passive"))
      (node (ref "FB1") (pin "2") (pinfunction "2_2") (pintype "passive"))
      (node (ref "U2") (pin "15") (pinfunction "VCC_AUXOUT_15") (pintype "power_in"))
    )
    (net (code "34") (name "/VCC_IN_PRI") (class "Default")
      (node (ref "C31") (pin "1") (pinfunction "1_1") (pintype "passive"))
      (node (ref "C32") (pin "1") (pinfunction "1_1") (pintype "passive"))
      (node (ref "FB6") (pin "2") (pinfunction "2_2") (pintype "passive"))
      (node (ref "U2") (pin "1") (pinfunction "VCC_IN_SEC_1") (pintype "power_in"))
      (node (ref "U2") (pin "47") (pinfunction "VCC_IN_PRI_47") (pintype "power_in"))
    )
    (net (code "35") (name "/VCC_OUT") (class "Default")
      (node (ref "C24") (pin "1") (pinfunction "1_1") (pintype "passive"))
      (node (ref "C25") (pin "1") (pinfunction "1_1") (pintype "passive"))
      (node (ref "C26") (pin "1") (pinfunction "1_1") (pintype "passive"))
      (node (ref "C27") (pin "1") (pinfunction "1_1") (pintype "passive"))
      (node (ref "C309") (pin "1") (pinfunction "1_1") (pintype "passive"))
      (node (ref "C310") (pin "1") (pinfunction "1_1") (pintype "passive"))
      (node (ref "C312") (pin "1") (pinfunction "1_1") (pintype "passive"))
      (node (ref "C313") (pin "1") (pinfunction "1_1") (pintype "passive"))
      (node (ref "FB4") (pin "2") (pinfunction "2_2") (pintype "passive"))
      (node (ref "U2") (pin "11") (pinfunction "VCC_OUT_11") (pintype "power_in"))
      (node (ref "U2") (pin "18") (pinfunction "VCC_OUT_18") (pintype "power_in"))
      (node (ref "U2") (pin "21") (pinfunction "VCC_OUT_21") (pintype "power_in"))
      (node (ref "U2") (pin "26") (pinfunction "VCC_OUT_26") (pintype "power_in"))
      (node (ref "U2") (pin "29") (pinfunction "VCC_OUT_29") (pintype "power_in"))
      (node (ref "U2") (pin "32") (pinfunction "VCC_OUT_32") (pintype "power_in"))
      (node (ref "U2") (pin "8") (pinfunction "VCC_OUT_8") (pintype "power_in"))
    )
    (net (code "36") (name "/VCC_VCO") (class "Default")
      (node (ref "C12") (pin "1") (pinfunction "1_1") (pintype "passive"))
      (node (ref "C20") (pin "1") (pinfunction "1_1") (pintype "passive"))
      (node (ref "C21") (pin "1") (pinfunction "1_1") (pintype "passive"))
      (node (ref "C22") (pin "1") (pinfunction "1_1") (pintype "passive"))
      (node (ref "FB3") (pin "2") (pinfunction "2_2") (pintype "passive"))
      (node (ref "U2") (pin "34") (pinfunction "VCC_VCO_34") (pintype "power_in"))
      (node (ref "U2") (pin "35") (pinfunction "VCC_VCO_35") (pintype "power_in"))
    )
    (net (code "37") (name "/VDD") (class "Default")
      (node (ref "C265") (pin "1") (pinfunction "1_1") (pintype "passive"))
      (node (ref "C306") (pin "1") (pinfunction "1_1") (pintype "passive"))
      (node (ref "FB25") (pin "2") (pinfunction "2_2") (pintype "passive"))
      (node (ref "U4") (pin "11") (pinfunction "VDD2_11") (pintype "power_in"))
      (node (ref "U4") (pin "14") (pinfunction "VDD1_2_14") (pintype "power_in"))
      (node (ref "U4") (pin "17") (pinfunction "VDD1_17") (pintype "power_in"))
      (node (ref "U4") (pin "8") (pinfunction "VDD2_2_8") (pintype "power_in"))
    )
    (net (code "38") (name "GND") (class "Default")
      (node (ref "C12") (pin "2") (pinfunction "2_2") (pintype "passive"))
      (node (ref "C15") (pin "2") (pinfunction "2_2") (pintype "passive"))
      (node (ref "C16") (pin "2") (pinfunction "2_2") (pintype "passive"))
      (node (ref "C17") (pin "2") (pinfunction "2_2") (pintype "passive"))
      (node (ref "C18") (pin "2") (pinfunction "2_2") (pintype "passive"))
      (node (ref "C20") (pin "2") (pinfunction "2_2") (pintype "passive"))
      (node (ref "C21") (pin "2") (pinfunction "2_2") (pintype "passive"))
      (node (ref "C22") (pin "2") (pinfunction "2_2") (pintype "passive"))
      (node (ref "C24") (pin "2") (pinfunction "2_2") (pintype "passive"))
      (node (ref "C25") (pin "2") (pinfunction "2_2") (pintype "passive"))
      (node (ref "C26") (pin "2") (pinfunction "2_2") (pintype "passive"))
      (node (ref "C265") (pin "2") (pinfunction "2_2") (pintype "passive"))
      (node (ref "C267") (pin "1") (pinfunction "1_1") (pintype "passive"))
      (node (ref "C268") (pin "1") (pinfunction "1_1") (pintype "passive"))
      (node (ref "C269") (pin "2") (pinfunction "2_2") (pintype "passive"))
      (node (ref "C27") (pin "2") (pinfunction "2_2") (pintype "passive"))
      (node (ref "C270") (pin "2") (pinfunction "2_2") (pintype "passive"))
      (node (ref "C271") (pin "2") (pinfunction "2_2") (pintype "passive"))
      (node (ref "C272") (pin "2") (pinfunction "2_2") (pintype "passive"))
      (node (ref "C273") (pin "2") (pinfunction "2_2") (pintype "passive"))
      (node (ref "C275") (pin "1") (pinfunction "1_1") (pintype "passive"))
      (node (ref "C28") (pin "2") (pinfunction "2_2") (pintype "passive"))
      (node (ref "C29") (pin "2") (pinfunction "2_2") (pintype "passive"))
      (node (ref "C306") (pin "2") (pinfunction "2_2") (pintype "passive"))
      (node (ref "C309") (pin "2") (pinfunction "2_2") (pintype "passive"))
      (node (ref "C31") (pin "2") (pinfunction "2_2") (pintype "passive"))
      (node (ref "C310") (pin "2") (pinfunction "2_2") (pintype "passive"))
      (node (ref "C311") (pin "2") (pinfunction "2_2") (pintype "passive"))
      (node (ref "C312") (pin "2") (pinfunction "2_2") (pintype "passive"))
      (node (ref "C313") (pin "2") (pinfunction "2_2") (pintype "passive"))
      (node (ref "C314") (pin "2") (pinfunction "2_2") (pintype "passive"))
      (node (ref "C315") (pin "2") (pinfunction "2_2") (pintype "passive"))
      (node (ref "C32") (pin "2") (pinfunction "2_2") (pintype "passive"))
      (node (ref "D1") (pin "1") (pinfunction "C_1") (pintype "passive"))
      (node (ref "J25") (pin "2") (pinfunction "MNT_1_2") (pintype "passive"))
      (node (ref "J3") (pin "2") (pinfunction "MNT_1_2") (pintype "passive"))
      (node (ref "J3") (pin "3") (pinfunction "MNT_2_3") (pintype "passive"))
      (node (ref "J5") (pin "2") (pinfunction "2_2") (pintype "passive"))
      (node (ref "J5") (pin "3") (pinfunction "3_3") (pintype "passive"))
      (node (ref "J5") (pin "4") (pinfunction "4_4") (pintype "passive"))
      (node (ref "J5") (pin "5") (pinfunction "5_5") (pintype "passive"))
      (node (ref "P13") (pin "3") (pinfunction "3_3") (pintype "passive"))
      (node (ref "P14") (pin "3") (pinfunction "3_3") (pintype "passive"))
      (node (ref "P15") (pin "3") (pinfunction "3_3") (pintype "passive"))
      (node (ref "P8") (pin "1") (pinfunction "1_1") (pintype "passive"))
      (node (ref "P9") (pin "3") (pinfunction "3_3") (pintype "passive"))
      (node (ref "R112") (pin "1") (pinfunction "1_1") (pintype "passive"))
      (node (ref "R113") (pin "1") (pinfunction "1_1") (pintype "passive"))
      (node (ref "R114") (pin "1") (pinfunction "1_1") (pintype "passive"))
      (node (ref "R115") (pin "1") (pinfunction "1_1") (pintype "passive"))
      (node (ref "R118") (pin "1") (pinfunction "1_1") (pintype "passive"))
      (node (ref "R119") (pin "1") (pinfunction "1_1") (pintype "passive"))
      (node (ref "R126") (pin "2") (pinfunction "2_2") (pintype "passive"))
      (node (ref "R24") (pin "1") (pinfunction "1_1") (pintype "passive"))
      (node (ref "R26") (pin "1") (pinfunction "1_1") (pintype "passive"))
      (node (ref "R27") (pin "1") (pinfunction "1_1") (pintype "passive"))
      (node (ref "R29") (pin "1") (pinfunction "1_1") (pintype "passive"))
      (node (ref "R39") (pin "1") (pinfunction "1_1") (pintype "passive"))
      (node (ref "R53") (pin "1") (pinfunction "1_1") (pintype "passive"))
      (node (ref "R85") (pin "1") (pinfunction "1_1") (pintype "passive"))
      (node (ref "R89") (pin "1") (pinfunction "1_1") (pintype "passive"))
      (node (ref "R90") (pin "1") (pinfunction "1_1") (pintype "passive"))
      (node (ref "R96") (pin "1") (pinfunction "1_1") (pintype "passive"))
      (node (ref "R97") (pin "1") (pinfunction "1_1") (pintype "passive"))
      (node (ref "R98") (pin "1") (pinfunction "1_1") (pintype "passive"))
      (node (ref "U2") (pin "2") (pinfunction "SEC_REF-_2") (pintype "passive"))
      (node (ref "U2") (pin "36") (pinfunction "GND_VCO_36") (pintype "power_in"))
      (node (ref "U2") (pin "43") (pinfunction "AUX_IN_43") (pintype "input"))
      (node (ref "U2") (pin "49") (pinfunction "GND_49") (pintype "power_in"))
      (node (ref "U4") (pin "13") (pinfunction "VSS_13") (pintype "passive"))
      (node (ref "U4") (pin "20") (pinfunction "VDD0_2_20") (pintype "power_in"))
      (node (ref "U4") (pin "23") (pinfunction "VDD0_23") (pintype "power_in"))
      (node (ref "U4") (pin "25") (pinfunction "EP_25") (pintype "passive"))
      (node (ref "U4") (pin "7") (pinfunction "VSS_2_7") (pintype "passive"))
    )
    (net (code "39") (name "Net-(C23-Pad2)") (class "Default")
      (node (ref "C23") (pin "2") (pinfunction "2_2") (pintype "passive"))
      (node (ref "J5") (pin "1") (pinfunction "1_1") (pintype "passive"))
      (node (ref "R27") (pin "2") (pinfunction "2_2") (pintype "passive"))
    )
    (net (code "40") (name "Net-(C30-Pad1)") (class "Default")
      (node (ref "C30") (pin "1") (pinfunction "1_1") (pintype "passive"))
      (node (ref "R30") (pin "2") (pinfunction "2_2") (pintype "passive"))
    )
    (net (code "41") (name "Net-(C275-Pad2)") (class "Default")
      (node (ref "C275") (pin "2") (pinfunction "2_2") (pintype "passive"))
      (node (ref "R91") (pin "1") (pinfunction "1_1") (pintype "passive"))
      (node (ref "R92") (pin "1") (pinfunction "1_1") (pintype "passive"))
      (node (ref "R93") (pin "2") (pinfunction "2_2") (pintype "passive"))
    )
    (net (code "42") (name "Net-(D1-A)") (class "Default")
      (node (ref "D1") (pin "2") (pinfunction "A_2") (pintype "passive"))
      (node (ref "R31") (pin "2") (pinfunction "2_2") (pintype "passive"))
    )
    (net (code "43") (name "Net-(P8-Pad3)") (class "Default")
      (node (ref "P8") (pin "3") (pinfunction "3_3") (pintype "passive"))
      (node (ref "R28") (pin "1") (pinfunction "1_1") (pintype "passive"))
      (node (ref "R29") (pin "2") (pinfunction "2_2") (pintype "passive"))
    )
    (net (code "44") (name "Net-(P9-Pad1)") (class "Default")
      (node (ref "P9") (pin "1") (pinfunction "1_1") (pintype "passive"))
      (node (ref "R84") (pin "1") (pinfunction "1_1") (pintype "passive"))
      (node (ref "R85") (pin "2") (pinfunction "2_2") (pintype "passive"))
    )
    (net (code "45") (name "Net-(P13-Pad1)") (class "Default")
      (node (ref "P13") (pin "1") (pinfunction "1_1") (pintype "passive"))
      (node (ref "R88") (pin "1") (pinfunction "1_1") (pintype "passive"))
      (node (ref "R96") (pin "2") (pinfunction "2_2") (pintype "passive"))
    )
    (net (code "46") (name "Net-(P14-Pad1)") (class "Default")
      (node (ref "P14") (pin "1") (pinfunction "1_1") (pintype "passive"))
      (node (ref "R94") (pin "1") (pinfunction "1_1") (pintype "passive"))
      (node (ref "R97") (pin "2") (pinfunction "2_2") (pintype "passive"))
    )
    (net (code "47") (name "Net-(P15-Pad1)") (class "Default")
      (node (ref "P15") (pin "1") (pinfunction "1_1") (pintype "passive"))
      (node (ref "R95") (pin "1") (pinfunction "1_1") (pintype "passive"))
      (node (ref "R98") (pin "2") (pinfunction "2_2") (pintype "passive"))
    )
    (net (code "48") (name "Net-(U2-EXT_LFN)") (class "Default")
      (node (ref "C30") (pin "2") (pinfunction "2_2") (pintype "passive"))
      (node (ref "C33") (pin "2") (pinfunction "2_2") (pintype "passive"))
      (node (ref "U2") (pin "41") (pinfunction "EXT_LFN_41") (pintype "passive"))
    )
    (net (code "49") (name "Net-(U2-EXT_LFP)") (class "Default")
      (node (ref "C33") (pin "1") (pinfunction "1_1") (pintype "passive"))
      (node (ref "R30") (pin "1") (pinfunction "1_1") (pintype "passive"))
      (node (ref "U2") (pin "40") (pinfunction "EXT_LFP_40") (pintype "passive"))
    )
    (net (code "50") (name "Net-(U2-PLL_LOCK)") (class "Default")
      (node (ref "R31") (pin "1") (pinfunction "1_1") (pintype "passive"))
      (node (ref "U2") (pin "37") (pinfunction "PLL_LOCK_37") (pintype "output"))
    )
    (net (code "51") (name "Net-(U2-REF_SEL)") (class "Default")
      (node (ref "J3") (pin "1") (pinfunction "1_1") (pintype "passive"))
      (node (ref "U2") (pin "31") (pinfunction "REF_SEL_31") (pintype "input"))
    )
    (net (code "52") (name "Net-(U2-REG_CAP1)") (class "Default")
      (node (ref "C267") (pin "2") (pinfunction "2_2") (pintype "passive"))
      (node (ref "U2") (pin "4") (pinfunction "REG_CAP1_4") (pintype "passive"))
    )
    (net (code "53") (name "Net-(U2-REG_CAP2)") (class "Default")
      (node (ref "C268") (pin "2") (pinfunction "2_2") (pintype "passive"))
      (node (ref "U2") (pin "38") (pinfunction "REG_CAP2_38") (pintype "passive"))
    )
    (net (code "54") (name "Net-(U2-SEC_REF+)") (class "Default")
      (node (ref "C14") (pin "2") (pinfunction "2_2") (pintype "passive"))
      (node (ref "R23") (pin "1") (pinfunction "1_1") (pintype "passive"))
      (node (ref "R24") (pin "2") (pinfunction "2_2") (pintype "passive"))
      (node (ref "U2") (pin "3") (pinfunction "SEC_REF+_3") (pintype "passive"))
    )
    (net (code "55") (name "Net-(U4-IN)") (class "Default")
      (node (ref "C274") (pin "2") (pinfunction "2_2") (pintype "passive"))
      (node (ref "R91") (pin "2") (pinfunction "2_2") (pintype "passive"))
      (node (ref "U4") (pin "3") (pinfunction "IN_3") (pintype "input"))
    )
    (net (code "56") (name "Net-(U4-~{IN})") (class "Default")
      (node (ref "C276") (pin "2") (pinfunction "2_2") (pintype "passive"))
      (node (ref "R93") (pin "1") (pinfunction "1_1") (pintype "passive"))
      (node (ref "U4") (pin "4") (pinfunction "~{IN}_4") (pintype "input"))
    )
    (net (code "57") (name "Net-(Y1-GND{slash}Case)") (class "Default")
      (node (ref "C13") (pin "2") (pinfunction "2_2") (pintype "passive"))
      (node (ref "Y1") (pin "2") (pinfunction "GND/Case_2") (pintype "power_in"))
    )
    (net (code "58") (name "Net-(Y1-Output)") (class "Default")
      (node (ref "C13") (pin "1") (pinfunction "1_1") (pintype "passive"))
      (node (ref "C14") (pin "1") (pinfunction "1_1") (pintype "passive"))
      (node (ref "Y1") (pin "3") (pinfunction "Output_3") (pintype "output"))
    )
    (net (code "59") (name "Net-(Y1-~{STBY})") (class "Default")
      (node (ref "P2") (pin "1") (pinfunction "1_1") (pintype "passive"))
      (node (ref "Y1") (pin "1") (pinfunction "~{STBY}_1") (pintype "input"))
    )
    (net (code "60") (name "unconnected-(U2-AUX_OUT-Pad13)") (class "Default")
      (node (ref "U2") (pin "13") (pinfunction "AUX_OUT_13") (pintype "output"))
    )
    (net (code "61") (name "unconnected-(U4-NC-Pad12)") (class "Default")
      (node (ref "U4") (pin "12") (pinfunction "NC_12") (pintype "passive"))
    )
    (net (code "62") (name "unconnected-(U4-Y0-Pad21)") (class "Default")
      (node (ref "U4") (pin "21") (pinfunction "Y0_21") (pintype "output"))
    )
    (net (code "63") (name "unconnected-(U4-~{Y0}-Pad22)") (class "Default")
      (node (ref "U4") (pin "22") (pinfunction "~{Y0}_22") (pintype "output"))
    )
  )
)
